# 44TQFP.net
KiCad netlist of a schematic drawn in EAGLE
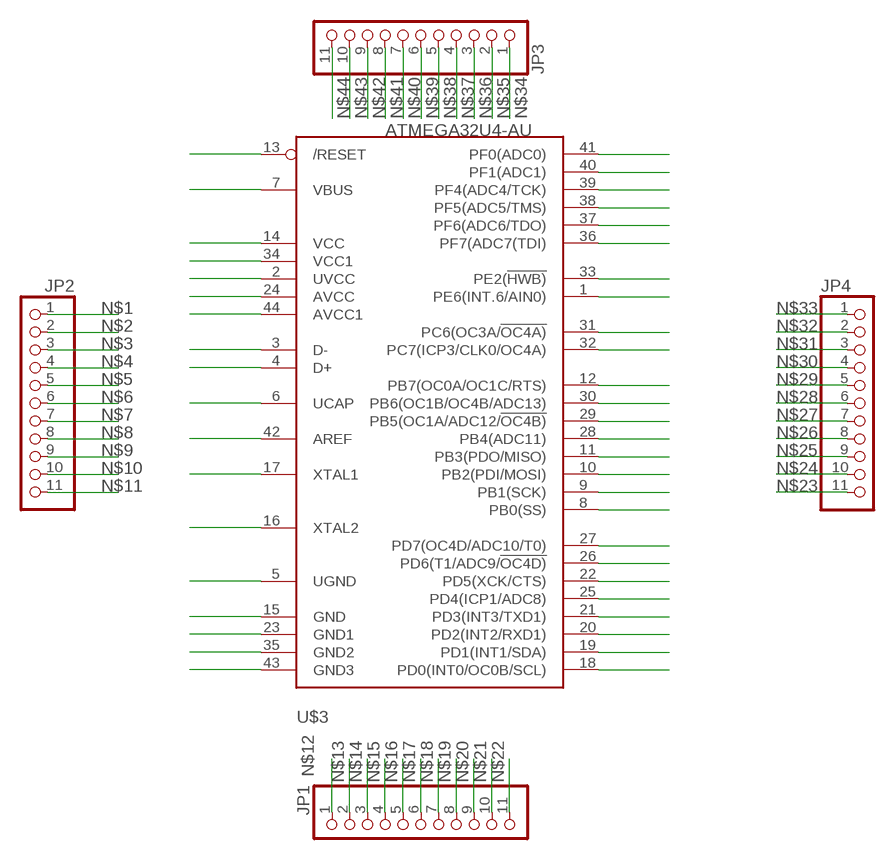
[diagram p0: schematic, sheet 1]

(export (version "E")
  (design (tool "Eeschema 10.0.6"))
  (components
    (comp (ref "JP1")
      (value "PINHD-1X11")
      (footprint "eagle-import:1X11")
      (libsource (lib "eagle-import") (part "PINHD-1X11"))
    )
    (comp (ref "JP2")
      (value "PINHD-1X11")
      (footprint "eagle-import:1X11")
      (libsource (lib "eagle-import") (part "PINHD-1X11"))
    )
    (comp (ref "JP3")
      (value "PINHD-1X11")
      (footprint "eagle-import:1X11")
      (libsource (lib "eagle-import") (part "PINHD-1X11"))
    )
    (comp (ref "JP4")
      (value "PINHD-1X11")
      (footprint "eagle-import:1X11")
      (libsource (lib "eagle-import") (part "PINHD-1X11"))
    )
    (comp (ref "U$3")
      (value "ATMEGA32U4-AU")
      (footprint "eagle-import:TQFP44")
      (libsource (lib "eagle-import") (part "ATMEGA32U4-AU"))
    )
  )
  (nets
    (net (code "1") (name "/N$1") (class "Default")
      (node (ref "JP2") (pin "1") (pinfunction "1_1") (pintype "passive"))
      (node (ref "U$3") (pin "1") (pinfunction "PE6(INT.6/AIN0)_1") (pintype "bidirectional"))
    )
    (net (code "2") (name "/N$2") (class "Default")
      (node (ref "JP2") (pin "2") (pinfunction "2_2") (pintype "passive"))
      (node (ref "U$3") (pin "2") (pinfunction "UVCC_2") (pintype "bidirectional"))
    )
    (net (code "3") (name "/N$3") (class "Default")
      (node (ref "JP2") (pin "3") (pinfunction "3_3") (pintype "passive"))
      (node (ref "U$3") (pin "3") (pinfunction "D-_3") (pintype "bidirectional"))
    )
    (net (code "4") (name "/N$4") (class "Default")
      (node (ref "JP2") (pin "4") (pinfunction "4_4") (pintype "passive"))
      (node (ref "U$3") (pin "4") (pinfunction "D+_4") (pintype "bidirectional"))
    )
    (net (code "5") (name "/N$5") (class "Default")
      (node (ref "JP2") (pin "5") (pinfunction "5_5") (pintype "passive"))
      (node (ref "U$3") (pin "5") (pinfunction "UGND_5") (pintype "bidirectional"))
    )
    (net (code "6") (name "/N$6") (class "Default")
      (node (ref "JP2") (pin "6") (pinfunction "6_6") (pintype "passive"))
      (node (ref "U$3") (pin "6") (pinfunction "UCAP_6") (pintype "bidirectional"))
    )
    (net (code "7") (name "/N$7") (class "Default")
      (node (ref "JP2") (pin "7") (pinfunction "7_7") (pintype "passive"))
      (node (ref "U$3") (pin "7") (pinfunction "VBUS_7") (pintype "bidirectional"))
    )
    (net (code "8") (name "/N$8") (class "Default")
      (node (ref "JP2") (pin "8") (pinfunction "8_8") (pintype "passive"))
      (node (ref "U$3") (pin "8") (pinfunction "PB0(SS)_8") (pintype "bidirectional"))
    )
    (net (code "9") (name "/N$9") (class "Default")
      (node (ref "JP2") (pin "9") (pinfunction "9_9") (pintype "passive"))
      (node (ref "U$3") (pin "9") (pinfunction "PB1(SCK)_9") (pintype "bidirectional"))
    )
    (net (code "10") (name "/N$10") (class "Default")
      (node (ref "JP2") (pin "10") (pinfunction "10_10") (pintype "passive"))
      (node (ref "U$3") (pin "10") (pinfunction "PB2(PDI/MOSI)_10") (pintype "bidirectional"))
    )
    (net (code "11") (name "/N$11") (class "Default")
      (node (ref "JP2") (pin "11") (pinfunction "11_11") (pintype "passive"))
      (node (ref "U$3") (pin "11") (pinfunction "PB3(PDO/MISO)_11") (pintype "bidirectional"))
    )
    (net (code "12") (name "/N$12") (class "Default")
      (node (ref "JP1") (pin "1") (pinfunction "1_1") (pintype "passive"))
      (node (ref "U$3") (pin "12") (pinfunction "PB7(OC0A/OC1C/RTS)_12") (pintype "bidirectional"))
    )
    (net (code "13") (name "/N$13") (class "Default")
      (node (ref "JP1") (pin "2") (pinfunction "2_2") (pintype "passive"))
      (node (ref "U$3") (pin "13") (pinfunction "/RESET_13") (pintype "bidirectional"))
    )
    (net (code "14") (name "/N$14") (class "Default")
      (node (ref "JP1") (pin "3") (pinfunction "3_3") (pintype "passive"))
      (node (ref "U$3") (pin "14") (pinfunction "VCC_14") (pintype "bidirectional"))
    )
    (net (code "15") (name "/N$15") (class "Default")
      (node (ref "JP1") (pin "4") (pinfunction "4_4") (pintype "passive"))
      (node (ref "U$3") (pin "15") (pinfunction "GND_15") (pintype "bidirectional"))
    )
    (net (code "16") (name "/N$16") (class "Default")
      (node (ref "JP1") (pin "5") (pinfunction "5_5") (pintype "passive"))
      (node (ref "U$3") (pin "16") (pinfunction "XTAL2_16") (pintype "bidirectional"))
    )
    (net (code "17") (name "/N$17") (class "Default")
      (node (ref "JP1") (pin "6") (pinfunction "6_6") (pintype "passive"))
      (node (ref "U$3") (pin "17") (pinfunction "XTAL1_17") (pintype "bidirectional"))
    )
    (net (code "18") (name "/N$18") (class "Default")
      (node (ref "JP1") (pin "7") (pinfunction "7_7") (pintype "passive"))
      (node (ref "U$3") (pin "18") (pinfunction "PD0(INT0/OC0B/SCL)_18") (pintype "bidirectional"))
    )
    (net (code "19") (name "/N$19") (class "Default")
      (node (ref "JP1") (pin "8") (pinfunction "8_8") (pintype "passive"))
      (node (ref "U$3") (pin "19") (pinfunction "PD1(INT1/SDA)_19") (pintype "bidirectional"))
    )
    (net (code "20") (name "/N$20") (class "Default")
      (node (ref "JP1") (pin "9") (pinfunction "9_9") (pintype "passive"))
      (node (ref "U$3") (pin "20") (pinfunction "PD2(INT2/RXD1)_20") (pintype "bidirectional"))
    )
    (net (code "21") (name "/N$21") (class "Default")
      (node (ref "JP1") (pin "10") (pinfunction "10_10") (pintype "passive"))
      (node (ref "U$3") (pin "21") (pinfunction "PD3(INT3/TXD1)_21") (pintype "bidirectional"))
    )
    (net (code "22") (name "/N$22") (class "Default")
      (node (ref "JP1") (pin "11") (pinfunction "11_11") (pintype "passive"))
      (node (ref "U$3") (pin "22") (pinfunction "PD5(XCK/CTS)_22") (pintype "bidirectional"))
    )
    (net (code "23") (name "/N$23") (class "Default")
      (node (ref "JP4") (pin "11") (pinfunction "11_11") (pintype "passive"))
      (node (ref "U$3") (pin "23") (pinfunction "GND1_23") (pintype "bidirectional"))
    )
    (net (code "24") (name "/N$24") (class "Default")
      (node (ref "JP4") (pin "10") (pinfunction "10_10") (pintype "passive"))
      (node (ref "U$3") (pin "24") (pinfunction "AVCC_24") (pintype "bidirectional"))
    )
    (net (code "25") (name "/N$25") (class "Default")
      (node (ref "JP4") (pin "9") (pinfunction "9_9") (pintype "passive"))
      (node (ref "U$3") (pin "25") (pinfunction "PD4(ICP1/ADC8)_25") (pintype "bidirectional"))
    )
    (net (code "26") (name "/N$26") (class "Default")
      (node (ref "JP4") (pin "8") (pinfunction "8_8") (pintype "passive"))
      (node (ref "U$3") (pin "26") (pinfunction "PD6(T1/ADC9/~{OC4D})_26") (pintype "bidirectional"))
    )
    (net (code "27") (name "/N$27") (class "Default")
      (node (ref "JP4") (pin "7") (pinfunction "7_7") (pintype "passive"))
      (node (ref "U$3") (pin "27") (pinfunction "PD7(OC4D/ADC10/T0)_27") (pintype "bidirectional"))
    )
    (net (code "28") (name "/N$28") (class "Default")
      (node (ref "JP4") (pin "6") (pinfunction "6_6") (pintype "passive"))
      (node (ref "U$3") (pin "28") (pinfunction "PB4(ADC11)_28") (pintype "bidirectional"))
    )
    (net (code "29") (name "/N$29") (class "Default")
      (node (ref "JP4") (pin "5") (pinfunction "5_5") (pintype "passive"))
      (node (ref "U$3") (pin "29") (pinfunction "PB5(OC1A/ADC12/~{OC4B})_29") (pintype "bidirectional"))
    )
    (net (code "30") (name "/N$30") (class "Default")
      (node (ref "JP4") (pin "4") (pinfunction "4_4") (pintype "passive"))
      (node (ref "U$3") (pin "30") (pinfunction "PB6(OC1B/OC4B/ADC13)_30") (pintype "bidirectional"))
    )
    (net (code "31") (name "/N$31") (class "Default")
      (node (ref "JP4") (pin "3") (pinfunction "3_3") (pintype "passive"))
      (node (ref "U$3") (pin "31") (pinfunction "PC6(OC3A/~{OC4A})_31") (pintype "bidirectional"))
    )
    (net (code "32") (name "/N$32") (class "Default")
      (node (ref "JP4") (pin "2") (pinfunction "2_2") (pintype "passive"))
      (node (ref "U$3") (pin "32") (pinfunction "PC7(ICP3/CLK0/OC4A)_32") (pintype "bidirectional"))
    )
    (net (code "33") (name "/N$33") (class "Default")
      (node (ref "JP4") (pin "1") (pinfunction "1_1") (pintype "passive"))
      (node (ref "U$3") (pin "33") (pinfunction "PE2(~{HWB})_33") (pintype "bidirectional"))
    )
    (net (code "34") (name "/N$34") (class "Default")
      (node (ref "JP3") (pin "1") (pinfunction "1_1") (pintype "passive"))
      (node (ref "U$3") (pin "34") (pinfunction "VCC1_34") (pintype "bidirectional"))
    )
    (net (code "35") (name "/N$35") (class "Default")
      (node (ref "JP3") (pin "2") (pinfunction "2_2") (pintype "passive"))
      (node (ref "U$3") (pin "35") (pinfunction "GND2_35") (pintype "bidirectional"))
    )
    (net (code "36") (name "/N$36") (class "Default")
      (node (ref "JP3") (pin "3") (pinfunction "3_3") (pintype "passive"))
      (node (ref "U$3") (pin "36") (pinfunction "PF7(ADC7(TDI)_36") (pintype "bidirectional"))
    )
    (net (code "37") (name "/N$37") (class "Default")
      (node (ref "JP3") (pin "4") (pinfunction "4_4") (pintype "passive"))
      (node (ref "U$3") (pin "37") (pinfunction "PF6(ADC6/TDO)_37") (pintype "bidirectional"))
    )
    (net (code "38") (name "/N$38") (class "Default")
      (node (ref "JP3") (pin "5") (pinfunction "5_5") (pintype "passive"))
      (node (ref "U$3") (pin "38") (pinfunction "PF5(ADC5/TMS)_38") (pintype "bidirectional"))
    )
    (net (code "39") (name "/N$39") (class "Default")
      (node (ref "JP3") (pin "6") (pinfunction "6_6") (pintype "passive"))
      (node (ref "U$3") (pin "39") (pinfunction "PF4(ADC4/TCK)_39") (pintype "bidirectional"))
    )
    (net (code "40") (name "/N$40") (class "Default")
      (node (ref "JP3") (pin "7") (pinfunction "7_7") (pintype "passive"))
      (node (ref "U$3") (pin "40") (pinfunction "PF1(ADC1)_40") (pintype "bidirectional"))
    )
    (net (code "41") (name "/N$41") (class "Default")
      (node (ref "JP3") (pin "8") (pinfunction "8_8") (pintype "passive"))
      (node (ref "U$3") (pin "41") (pinfunction "PF0(ADC0)_41") (pintype "bidirectional"))
    )
    (net (code "42") (name "/N$42") (class "Default")
      (node (ref "JP3") (pin "9") (pinfunction "9_9") (pintype "passive"))
      (node (ref "U$3") (pin "42") (pinfunction "AREF_42") (pintype "bidirectional"))
    )
    (net (code "43") (name "/N$43") (class "Default")
      (node (ref "JP3") (pin "10") (pinfunction "10_10") (pintype "passive"))
      (node (ref "U$3") (pin "43") (pinfunction "GND3_43") (pintype "bidirectional"))
    )
    (net (code "44") (name "/N$44") (class "Default")
      (node (ref "JP3") (pin "11") (pinfunction "11_11") (pintype "passive"))
      (node (ref "U$3") (pin "44") (pinfunction "AVCC1_44") (pintype "bidirectional"))
    )
  )
)
